# TurntableStrobe.net
KiCad netlist of a schematic drawn in EAGLE
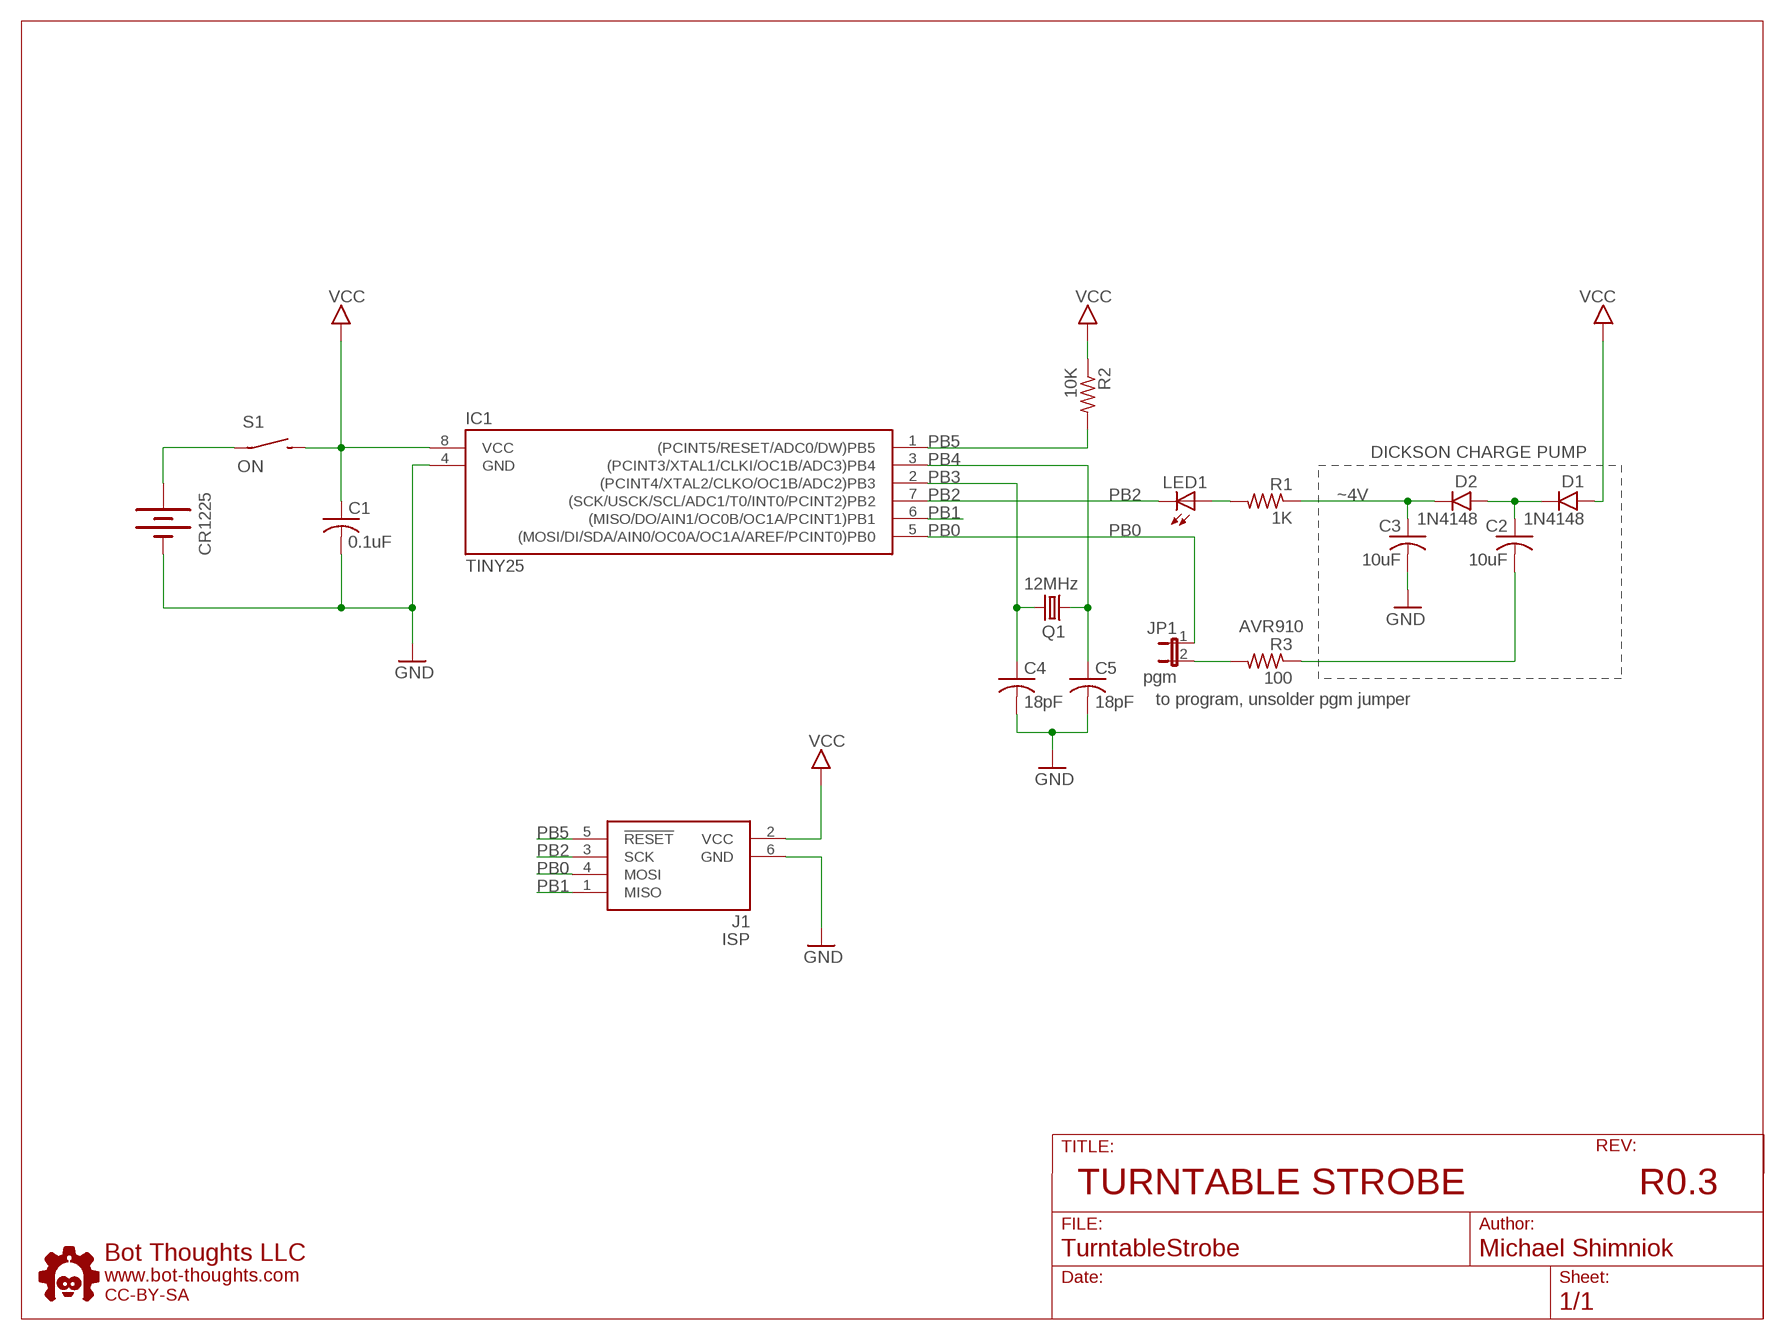
[diagram p0: schematic, sheet 1]

(export (version "E")
  (design (tool "Eeschema 10.0.6"))
  (components
    (comp (ref "C1")
      (value "0.1uF")
      (footprint "eagle-import:C0603")
      (libsource (lib "eagle-import") (part "C-USC0603"))
    )
    (comp (ref "C2")
      (value "10uF")
      (footprint "eagle-import:C0603")
      (libsource (lib "eagle-import") (part "C-USC0603"))
    )
    (comp (ref "C3")
      (value "10uF")
      (footprint "eagle-import:C0603")
      (libsource (lib "eagle-import") (part "C-USC0603"))
    )
    (comp (ref "C4")
      (value "18pF")
      (footprint "eagle-import:C0603")
      (libsource (lib "eagle-import") (part "C-USC0603"))
    )
    (comp (ref "C5")
      (value "18pF")
      (footprint "eagle-import:C0603")
      (libsource (lib "eagle-import") (part "C-USC0603"))
    )
    (comp (ref "CR1225")
      (value "BATTERY12PTH")
      (footprint "eagle-import:BATTCON_12MM_PTH")
      (libsource (lib "eagle-import") (part "BATTERY12PTH"))
    )
    (comp (ref "D1")
      (value "1N4148")
      (footprint "eagle-import:SOD-323")
      (libsource (lib "eagle-import") (part "DIODE_SOD323"))
    )
    (comp (ref "D2")
      (value "1N4148")
      (footprint "eagle-import:SOD-323")
      (libsource (lib "eagle-import") (part "DIODE_SOD323"))
    )
    (comp (ref "IC1")
      (value "TINY25")
      (footprint "eagle-import:SOIC8N")
      (libsource (lib "eagle-import") (part "TINY25/45/85-20SSU"))
    )
    (comp (ref "J1")
      (value "ISP")
      (footprint "eagle-import:2X3_TP")
      (libsource (lib "eagle-import") (part "AVRISP6_TP"))
    )
    (comp (ref "JP1")
      (value "pgm")
      (footprint "eagle-import:SJ_2S-NO")
      (libsource (lib "eagle-import") (part "JUMPER-2SMD-NO"))
    )
    (comp (ref "LED1")
      (value "LED5MMRA")
      (footprint "eagle-import:LED5MMRA")
      (libsource (lib "eagle-import") (part "LED5MMRA"))
    )
    (comp (ref "Q1")
      (value "12MHz")
      (footprint "eagle-import:NDK_2PAD_5X3")
      (libsource (lib "eagle-import") (part "CRYSTALNDK5X3"))
    )
    (comp (ref "R1")
      (value "1K")
      (footprint "eagle-import:R0603")
      (libsource (lib "eagle-import") (part "R-US_R0603"))
    )
    (comp (ref "R2")
      (value "10K")
      (footprint "eagle-import:R0603")
      (libsource (lib "eagle-import") (part "R-US_R0603"))
    )
    (comp (ref "R3")
      (value "100")
      (footprint "eagle-import:R0603")
      (libsource (lib "eagle-import") (part "R-US_R0603"))
    )
    (comp (ref "S1")
      (value "ON")
      (footprint "eagle-import:6MMTACTILE_RECT")
      (libsource (lib "eagle-import") (part "SPST_TAC_RECT1"))
    )
    (comp (ref "U$5")
      (value "BTLOGO-LOGO-MD")
      (footprint "eagle-import:BTLOGOM")
      (libsource (lib "eagle-import") (part "BTLOGO-LOGO-MD"))
    )
  )
  (nets
    (net (code "1") (name "/PB0") (class "Default")
      (node (ref "IC1") (pin "5") (pinfunction "(MOSI/DI/SDA/AIN0/OC0A/OC1A/AREF/PCINT0)PB0_5") (pintype "bidirectional"))
      (node (ref "J1") (pin "4") (pinfunction "MOSI_4") (pintype "output"))
      (node (ref "JP1") (pin "1") (pinfunction "1_1") (pintype "passive"))
    )
    (net (code "2") (name "/PB1") (class "Default")
      (node (ref "IC1") (pin "6") (pinfunction "(MISO/DO/AIN1/OC0B/OC1A/PCINT1)PB1_6") (pintype "bidirectional"))
      (node (ref "J1") (pin "1") (pinfunction "MISO_1") (pintype "input"))
    )
    (net (code "3") (name "/PB2") (class "Default")
      (node (ref "IC1") (pin "7") (pinfunction "(SCK/USCK/SCL/ADC1/T0/INT0/PCINT2)PB2_7") (pintype "bidirectional"))
      (node (ref "J1") (pin "3") (pinfunction "SCK_3") (pintype "output"))
      (node (ref "LED1") (pin "C") (pinfunction "C_C") (pintype "passive"))
    )
    (net (code "4") (name "/PB3") (class "Default")
      (node (ref "C4") (pin "1") (pinfunction "1_1") (pintype "passive"))
      (node (ref "IC1") (pin "2") (pinfunction "(PCINT4/XTAL2/CLKO/OC1B/ADC2)PB3_2") (pintype "bidirectional"))
      (node (ref "Q1") (pin "P$2") (pinfunction "2_P$2") (pintype "passive"))
    )
    (net (code "5") (name "/PB4") (class "Default")
      (node (ref "C5") (pin "1") (pinfunction "1_1") (pintype "passive"))
      (node (ref "IC1") (pin "3") (pinfunction "(PCINT3/XTAL1/CLKI/OC1B/ADC3)PB4_3") (pintype "bidirectional"))
      (node (ref "Q1") (pin "P$1") (pinfunction "1_P$1") (pintype "passive"))
    )
    (net (code "6") (name "/PB5") (class "Default")
      (node (ref "IC1") (pin "1") (pinfunction "(PCINT5/RESET/ADC0/DW)PB5_1") (pintype "bidirectional"))
      (node (ref "J1") (pin "5") (pinfunction "~{RESET}_5") (pintype "output"))
      (node (ref "R2") (pin "2") (pinfunction "2_2") (pintype "passive"))
    )
    (net (code "7") (name "GND") (class "Default")
      (node (ref "C1") (pin "2") (pinfunction "2_2") (pintype "passive"))
      (node (ref "C3") (pin "2") (pinfunction "2_2") (pintype "passive"))
      (node (ref "C4") (pin "2") (pinfunction "2_2") (pintype "passive"))
      (node (ref "C5") (pin "2") (pinfunction "2_2") (pintype "passive"))
      (node (ref "CR1225") (pin "GND") (pinfunction "-_GND") (pintype "power_in"))
      (node (ref "IC1") (pin "4") (pinfunction "GND_4") (pintype "power_in"))
      (node (ref "J1") (pin "6") (pinfunction "GND_6") (pintype "power_in"))
    )
    (net (code "8") (name "Net-(C2-Pad1)") (class "Default")
      (node (ref "C2") (pin "1") (pinfunction "1_1") (pintype "passive"))
      (node (ref "D1") (pin "C") (pinfunction "C_C") (pintype "passive"))
      (node (ref "D2") (pin "A") (pinfunction "A_A") (pintype "passive"))
    )
    (net (code "9") (name "Net-(C2-Pad2)") (class "Default")
      (node (ref "C2") (pin "2") (pinfunction "2_2") (pintype "passive"))
      (node (ref "R3") (pin "1") (pinfunction "1_1") (pintype "passive"))
    )
    (net (code "10") (name "Net-(C3-Pad1)") (class "Default")
      (node (ref "C3") (pin "1") (pinfunction "1_1") (pintype "passive"))
      (node (ref "D2") (pin "C") (pinfunction "C_C") (pintype "passive"))
      (node (ref "R1") (pin "1") (pinfunction "1_1") (pintype "passive"))
    )
    (net (code "11") (name "Net-(CR1225-+)") (class "Default")
      (node (ref "CR1225") (pin "VCC@1") (pinfunction "+_VCC@1") (pintype "power_in"))
      (node (ref "S1") (pin "P$1") (pinfunction "P_P$1") (pintype "passive"))
    )
    (net (code "12") (name "Net-(JP1-Pad2)") (class "Default")
      (node (ref "JP1") (pin "2") (pinfunction "2_2") (pintype "passive"))
      (node (ref "R3") (pin "2") (pinfunction "2_2") (pintype "passive"))
    )
    (net (code "13") (name "Net-(LED1-PadA)") (class "Default")
      (node (ref "LED1") (pin "A") (pinfunction "A_A") (pintype "passive"))
      (node (ref "R1") (pin "2") (pinfunction "2_2") (pintype "passive"))
    )
    (net (code "14") (name "VCC") (class "Default")
      (node (ref "C1") (pin "1") (pinfunction "1_1") (pintype "passive"))
      (node (ref "D1") (pin "A") (pinfunction "A_A") (pintype "passive"))
      (node (ref "IC1") (pin "8") (pinfunction "VCC_8") (pintype "power_in"))
      (node (ref "J1") (pin "2") (pinfunction "VCC_2") (pintype "power_in"))
      (node (ref "R2") (pin "1") (pinfunction "1_1") (pintype "passive"))
      (node (ref "S1") (pin "P$2") (pinfunction "S_P$2") (pintype "passive"))
    )
  )
)
